# esquematico_ED3.net
KiCad netlist of a schematic drawn in Altium Designer
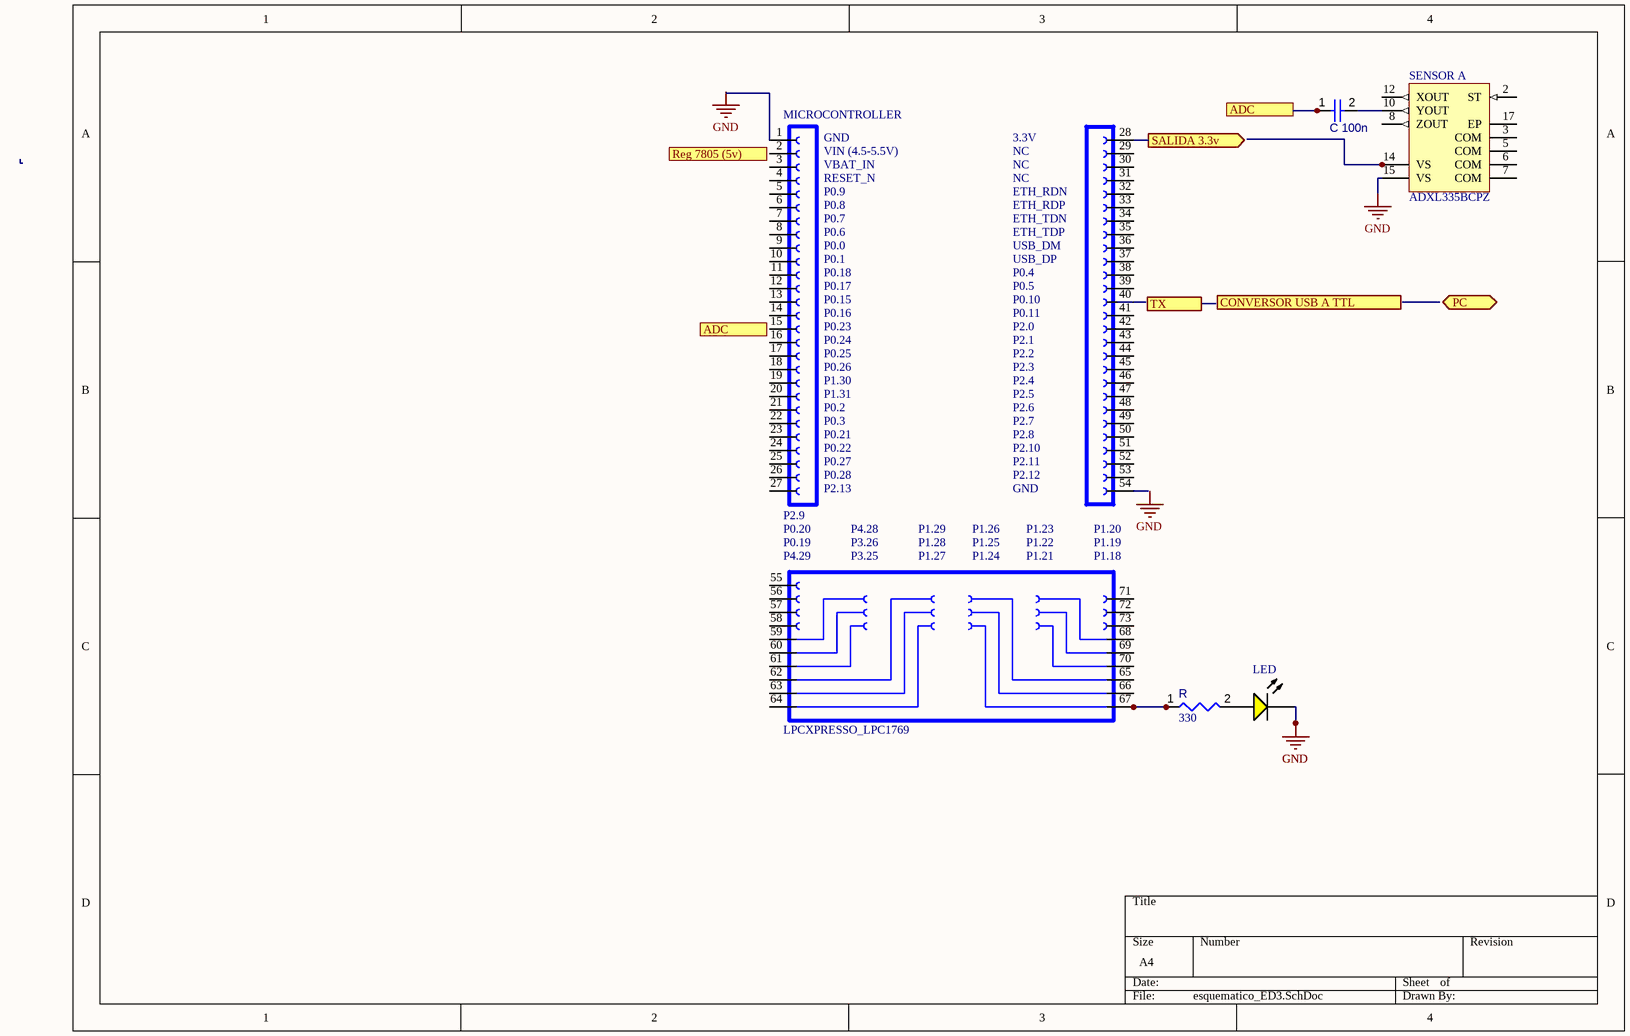
[diagram p0: esquematico_ED3.SchDoc]

(export (version "E")
  (design (tool "Eeschema 10.0.6"))
  (components
    (comp (ref "C 100n")
      (value "Capacitors")
      (description "Capacitor")
      (libsource (lib "Juana Pucheta Noguera") (part "CAP-NP-2"))
    )
    (comp (ref "LED")
      (value "~")
      (footprint "VISH-TLMX1100-2_V")
      (description "Yellow LED, 20 mA, 2.1 V, -40 to 100 degC, 2-Pin SMD (0603), RoHS, Tape and Reel")
      (fields (field (name "MANUFACTURER") "Vishay Semiconductor") (field (name "POWER") "90mW"))
      (libsource (lib "Juana Pucheta Noguera") (part "LED-YELLOW-AK-2"))
    )
    (comp (ref "MICROCONTROLLER")
      (value "LPCXPRESSO_LPC1769")
      (footprint "LPCXPRESSO_LPC1769")
      (fields (field (name "MF") "Embedded Artists") (field (name "MP") "LPCXPRESSO LPC1769"))
      (libsource (lib "LPCXPRESSO_LPC1769 (1)") (part "LPCXPRESSO_LPC1769"))
    )
    (comp (ref "R")
      (value "330")
      (footprint "RESC0402(1005)_L")
      (description "330R 0.063W 5% 0402 (1005 Metric)  SMD")
      (fields (field (name "TOLERANCE") "5%") (field (name "POWER") "63mW"))
      (libsource (lib "Juana Pucheta Noguera") (part "330R2J"))
    )
    (comp (ref "SENSOR")
      (value "ADXL335BCPZ")
      (footprint "ADI-CP-16-14_M")
      (fields (field (name "MANUFACTURER") "Analog Devices"))
      (libsource (lib "Juana Pucheta Noguera") (part "ADI-ADXL3XX-CP-16-XX"))
    )
  )
  (nets
    (net (code "5") (name "/SALIDA 3.3v") (class "Default")
      (node (ref "MICROCONTROLLER") (pin "28") (pinfunction "28_28") (pintype "passive"))
    )
    (net (code "7") (name "GND") (class "Default")
      (node (ref "LED") (pin "2") (pinfunction "K_2") (pintype "passive"))
      (node (ref "SENSOR") (pin "15") (pinfunction "VS_15") (pintype "power_in"))
    )
    (net (code "8") (name "Net-(MICROCONTROLLER-Pad67)") (class "Default")
      (node (ref "MICROCONTROLLER") (pin "67") (pinfunction "67_67") (pintype "passive"))
      (node (ref "R") (pin "1") (pinfunction "1_1") (pintype "passive"))
    )
    (net (code "9") (name "Net-(SENSORA-YOUT)") (class "Default")
      (node (ref "C 100n") (pin "2") (pinfunction "2_2") (pintype "passive"))
      (node (ref "SENSOR") (pin "10") (pinfunction "YOUT_10") (pintype "output"))
    )
    (net (code "10") (name "unconnected-(C 100n-Pad1)") (class "Default")
      (node (ref "C 100n") (pin "1") (pinfunction "1_1") (pintype "passive"))
    )
    (net (code "11") (name "unconnected-(LED-A-Pad1)") (class "Default")
      (node (ref "LED") (pin "1") (pinfunction "A_1") (pintype "passive"))
    )
    (net (code "12") (name "unconnected-(MICROCONTROLLER-Pad1)") (class "Default")
      (node (ref "MICROCONTROLLER") (pin "1") (pinfunction "1_1") (pintype "passive"))
    )
    (net (code "13") (name "unconnected-(MICROCONTROLLER-Pad2)") (class "Default")
      (node (ref "MICROCONTROLLER") (pin "2") (pinfunction "2_2") (pintype "passive"))
    )
    (net (code "14") (name "unconnected-(MICROCONTROLLER-Pad3)") (class "Default")
      (node (ref "MICROCONTROLLER") (pin "3") (pinfunction "3_3") (pintype "passive"))
    )
    (net (code "15") (name "unconnected-(MICROCONTROLLER-Pad4)") (class "Default")
      (node (ref "MICROCONTROLLER") (pin "4") (pinfunction "4_4") (pintype "passive"))
    )
    (net (code "16") (name "unconnected-(MICROCONTROLLER-Pad5)") (class "Default")
      (node (ref "MICROCONTROLLER") (pin "5") (pinfunction "5_5") (pintype "passive"))
    )
    (net (code "17") (name "unconnected-(MICROCONTROLLER-Pad6)") (class "Default")
      (node (ref "MICROCONTROLLER") (pin "6") (pinfunction "6_6") (pintype "passive"))
    )
    (net (code "18") (name "unconnected-(MICROCONTROLLER-Pad7)") (class "Default")
      (node (ref "MICROCONTROLLER") (pin "7") (pinfunction "7_7") (pintype "passive"))
    )
    (net (code "19") (name "unconnected-(MICROCONTROLLER-Pad8)") (class "Default")
      (node (ref "MICROCONTROLLER") (pin "8") (pinfunction "8_8") (pintype "passive"))
    )
    (net (code "20") (name "unconnected-(MICROCONTROLLER-Pad9)") (class "Default")
      (node (ref "MICROCONTROLLER") (pin "9") (pinfunction "9_9") (pintype "passive"))
    )
    (net (code "21") (name "unconnected-(MICROCONTROLLER-Pad10)") (class "Default")
      (node (ref "MICROCONTROLLER") (pin "10") (pinfunction "10_10") (pintype "passive"))
    )
    (net (code "22") (name "unconnected-(MICROCONTROLLER-Pad11)") (class "Default")
      (node (ref "MICROCONTROLLER") (pin "11") (pinfunction "11_11") (pintype "passive"))
    )
    (net (code "23") (name "unconnected-(MICROCONTROLLER-Pad12)") (class "Default")
      (node (ref "MICROCONTROLLER") (pin "12") (pinfunction "12_12") (pintype "passive"))
    )
    (net (code "24") (name "unconnected-(MICROCONTROLLER-Pad13)") (class "Default")
      (node (ref "MICROCONTROLLER") (pin "13") (pinfunction "13_13") (pintype "passive"))
    )
    (net (code "25") (name "unconnected-(MICROCONTROLLER-Pad14)") (class "Default")
      (node (ref "MICROCONTROLLER") (pin "14") (pinfunction "14_14") (pintype "passive"))
    )
    (net (code "26") (name "unconnected-(MICROCONTROLLER-Pad15)") (class "Default")
      (node (ref "MICROCONTROLLER") (pin "15") (pinfunction "15_15") (pintype "passive"))
    )
    (net (code "27") (name "unconnected-(MICROCONTROLLER-Pad16)") (class "Default")
      (node (ref "MICROCONTROLLER") (pin "16") (pinfunction "16_16") (pintype "passive"))
    )
    (net (code "28") (name "unconnected-(MICROCONTROLLER-Pad17)") (class "Default")
      (node (ref "MICROCONTROLLER") (pin "17") (pinfunction "17_17") (pintype "passive"))
    )
    (net (code "29") (name "unconnected-(MICROCONTROLLER-Pad18)") (class "Default")
      (node (ref "MICROCONTROLLER") (pin "18") (pinfunction "18_18") (pintype "passive"))
    )
    (net (code "30") (name "unconnected-(MICROCONTROLLER-Pad19)") (class "Default")
      (node (ref "MICROCONTROLLER") (pin "19") (pinfunction "19_19") (pintype "passive"))
    )
    (net (code "31") (name "unconnected-(MICROCONTROLLER-Pad20)") (class "Default")
      (node (ref "MICROCONTROLLER") (pin "20") (pinfunction "20_20") (pintype "passive"))
    )
    (net (code "32") (name "unconnected-(MICROCONTROLLER-Pad21)") (class "Default")
      (node (ref "MICROCONTROLLER") (pin "21") (pinfunction "21_21") (pintype "passive"))
    )
    (net (code "33") (name "unconnected-(MICROCONTROLLER-Pad22)") (class "Default")
      (node (ref "MICROCONTROLLER") (pin "22") (pinfunction "22_22") (pintype "passive"))
    )
    (net (code "34") (name "unconnected-(MICROCONTROLLER-Pad23)") (class "Default")
      (node (ref "MICROCONTROLLER") (pin "23") (pinfunction "23_23") (pintype "passive"))
    )
    (net (code "35") (name "unconnected-(MICROCONTROLLER-Pad24)") (class "Default")
      (node (ref "MICROCONTROLLER") (pin "24") (pinfunction "24_24") (pintype "passive"))
    )
    (net (code "36") (name "unconnected-(MICROCONTROLLER-Pad25)") (class "Default")
      (node (ref "MICROCONTROLLER") (pin "25") (pinfunction "25_25") (pintype "passive"))
    )
    (net (code "37") (name "unconnected-(MICROCONTROLLER-Pad26)") (class "Default")
      (node (ref "MICROCONTROLLER") (pin "26") (pinfunction "26_26") (pintype "passive"))
    )
    (net (code "38") (name "unconnected-(MICROCONTROLLER-Pad27)") (class "Default")
      (node (ref "MICROCONTROLLER") (pin "27") (pinfunction "27_27") (pintype "passive"))
    )
    (net (code "39") (name "unconnected-(MICROCONTROLLER-Pad29)") (class "Default")
      (node (ref "MICROCONTROLLER") (pin "29") (pinfunction "29_29") (pintype "passive"))
    )
    (net (code "40") (name "unconnected-(MICROCONTROLLER-Pad30)") (class "Default")
      (node (ref "MICROCONTROLLER") (pin "30") (pinfunction "30_30") (pintype "passive"))
    )
    (net (code "41") (name "unconnected-(MICROCONTROLLER-Pad31)") (class "Default")
      (node (ref "MICROCONTROLLER") (pin "31") (pinfunction "31_31") (pintype "passive"))
    )
    (net (code "42") (name "unconnected-(MICROCONTROLLER-Pad32)") (class "Default")
      (node (ref "MICROCONTROLLER") (pin "32") (pinfunction "32_32") (pintype "passive"))
    )
    (net (code "43") (name "unconnected-(MICROCONTROLLER-Pad33)") (class "Default")
      (node (ref "MICROCONTROLLER") (pin "33") (pinfunction "33_33") (pintype "passive"))
    )
    (net (code "44") (name "unconnected-(MICROCONTROLLER-Pad34)") (class "Default")
      (node (ref "MICROCONTROLLER") (pin "34") (pinfunction "34_34") (pintype "passive"))
    )
    (net (code "45") (name "unconnected-(MICROCONTROLLER-Pad35)") (class "Default")
      (node (ref "MICROCONTROLLER") (pin "35") (pinfunction "35_35") (pintype "passive"))
    )
    (net (code "46") (name "unconnected-(MICROCONTROLLER-Pad36)") (class "Default")
      (node (ref "MICROCONTROLLER") (pin "36") (pinfunction "36_36") (pintype "passive"))
    )
    (net (code "47") (name "unconnected-(MICROCONTROLLER-Pad37)") (class "Default")
      (node (ref "MICROCONTROLLER") (pin "37") (pinfunction "37_37") (pintype "passive"))
    )
    (net (code "48") (name "unconnected-(MICROCONTROLLER-Pad38)") (class "Default")
      (node (ref "MICROCONTROLLER") (pin "38") (pinfunction "38_38") (pintype "passive"))
    )
    (net (code "49") (name "unconnected-(MICROCONTROLLER-Pad39)") (class "Default")
      (node (ref "MICROCONTROLLER") (pin "39") (pinfunction "39_39") (pintype "passive"))
    )
    (net (code "50") (name "unconnected-(MICROCONTROLLER-Pad40)") (class "Default")
      (node (ref "MICROCONTROLLER") (pin "40") (pinfunction "40_40") (pintype "passive"))
    )
    (net (code "51") (name "unconnected-(MICROCONTROLLER-Pad41)") (class "Default")
      (node (ref "MICROCONTROLLER") (pin "41") (pinfunction "41_41") (pintype "passive"))
    )
    (net (code "52") (name "unconnected-(MICROCONTROLLER-Pad42)") (class "Default")
      (node (ref "MICROCONTROLLER") (pin "42") (pinfunction "42_42") (pintype "passive"))
    )
    (net (code "53") (name "unconnected-(MICROCONTROLLER-Pad43)") (class "Default")
      (node (ref "MICROCONTROLLER") (pin "43") (pinfunction "43_43") (pintype "passive"))
    )
    (net (code "54") (name "unconnected-(MICROCONTROLLER-Pad44)") (class "Default")
      (node (ref "MICROCONTROLLER") (pin "44") (pinfunction "44_44") (pintype "passive"))
    )
    (net (code "55") (name "unconnected-(MICROCONTROLLER-Pad45)") (class "Default")
      (node (ref "MICROCONTROLLER") (pin "45") (pinfunction "45_45") (pintype "passive"))
    )
    (net (code "56") (name "unconnected-(MICROCONTROLLER-Pad46)") (class "Default")
      (node (ref "MICROCONTROLLER") (pin "46") (pinfunction "46_46") (pintype "passive"))
    )
    (net (code "57") (name "unconnected-(MICROCONTROLLER-Pad47)") (class "Default")
      (node (ref "MICROCONTROLLER") (pin "47") (pinfunction "47_47") (pintype "passive"))
    )
    (net (code "58") (name "unconnected-(MICROCONTROLLER-Pad48)") (class "Default")
      (node (ref "MICROCONTROLLER") (pin "48") (pinfunction "48_48") (pintype "passive"))
    )
    (net (code "59") (name "unconnected-(MICROCONTROLLER-Pad49)") (class "Default")
      (node (ref "MICROCONTROLLER") (pin "49") (pinfunction "49_49") (pintype "passive"))
    )
    (net (code "60") (name "unconnected-(MICROCONTROLLER-Pad50)") (class "Default")
      (node (ref "MICROCONTROLLER") (pin "50") (pinfunction "50_50") (pintype "passive"))
    )
    (net (code "61") (name "unconnected-(MICROCONTROLLER-Pad51)") (class "Default")
      (node (ref "MICROCONTROLLER") (pin "51") (pinfunction "51_51") (pintype "passive"))
    )
    (net (code "62") (name "unconnected-(MICROCONTROLLER-Pad52)") (class "Default")
      (node (ref "MICROCONTROLLER") (pin "52") (pinfunction "52_52") (pintype "passive"))
    )
    (net (code "63") (name "unconnected-(MICROCONTROLLER-Pad53)") (class "Default")
      (node (ref "MICROCONTROLLER") (pin "53") (pinfunction "53_53") (pintype "passive"))
    )
    (net (code "64") (name "unconnected-(MICROCONTROLLER-Pad54)") (class "Default")
      (node (ref "MICROCONTROLLER") (pin "54") (pinfunction "54_54") (pintype "passive"))
    )
    (net (code "65") (name "unconnected-(MICROCONTROLLER-Pad55)") (class "Default")
      (node (ref "MICROCONTROLLER") (pin "55") (pinfunction "55_55") (pintype "passive"))
    )
    (net (code "66") (name "unconnected-(MICROCONTROLLER-Pad56)") (class "Default")
      (node (ref "MICROCONTROLLER") (pin "56") (pinfunction "56_56") (pintype "passive"))
    )
    (net (code "67") (name "unconnected-(MICROCONTROLLER-Pad57)") (class "Default")
      (node (ref "MICROCONTROLLER") (pin "57") (pinfunction "57_57") (pintype "passive"))
    )
    (net (code "68") (name "unconnected-(MICROCONTROLLER-Pad58)") (class "Default")
      (node (ref "MICROCONTROLLER") (pin "58") (pinfunction "58_58") (pintype "passive"))
    )
    (net (code "69") (name "unconnected-(MICROCONTROLLER-Pad59)") (class "Default")
      (node (ref "MICROCONTROLLER") (pin "59") (pinfunction "59_59") (pintype "passive"))
    )
    (net (code "70") (name "unconnected-(MICROCONTROLLER-Pad60)") (class "Default")
      (node (ref "MICROCONTROLLER") (pin "60") (pinfunction "60_60") (pintype "passive"))
    )
    (net (code "71") (name "unconnected-(MICROCONTROLLER-Pad61)") (class "Default")
      (node (ref "MICROCONTROLLER") (pin "61") (pinfunction "61_61") (pintype "passive"))
    )
    (net (code "72") (name "unconnected-(MICROCONTROLLER-Pad62)") (class "Default")
      (node (ref "MICROCONTROLLER") (pin "62") (pinfunction "62_62") (pintype "passive"))
    )
    (net (code "73") (name "unconnected-(MICROCONTROLLER-Pad63)") (class "Default")
      (node (ref "MICROCONTROLLER") (pin "63") (pinfunction "63_63") (pintype "passive"))
    )
    (net (code "74") (name "unconnected-(MICROCONTROLLER-Pad64)") (class "Default")
      (node (ref "MICROCONTROLLER") (pin "64") (pinfunction "64_64") (pintype "passive"))
    )
    (net (code "75") (name "unconnected-(MICROCONTROLLER-Pad65)") (class "Default")
      (node (ref "MICROCONTROLLER") (pin "65") (pinfunction "65_65") (pintype "passive"))
    )
    (net (code "76") (name "unconnected-(MICROCONTROLLER-Pad66)") (class "Default")
      (node (ref "MICROCONTROLLER") (pin "66") (pinfunction "66_66") (pintype "passive"))
    )
    (net (code "77") (name "unconnected-(MICROCONTROLLER-Pad68)") (class "Default")
      (node (ref "MICROCONTROLLER") (pin "68") (pinfunction "68_68") (pintype "passive"))
    )
    (net (code "78") (name "unconnected-(MICROCONTROLLER-Pad69)") (class "Default")
      (node (ref "MICROCONTROLLER") (pin "69") (pinfunction "69_69") (pintype "passive"))
    )
    (net (code "79") (name "unconnected-(MICROCONTROLLER-Pad70)") (class "Default")
      (node (ref "MICROCONTROLLER") (pin "70") (pinfunction "70_70") (pintype "passive"))
    )
    (net (code "80") (name "unconnected-(MICROCONTROLLER-Pad71)") (class "Default")
      (node (ref "MICROCONTROLLER") (pin "71") (pinfunction "71_71") (pintype "passive"))
    )
    (net (code "81") (name "unconnected-(MICROCONTROLLER-Pad72)") (class "Default")
      (node (ref "MICROCONTROLLER") (pin "72") (pinfunction "72_72") (pintype "passive"))
    )
    (net (code "82") (name "unconnected-(MICROCONTROLLER-Pad73)") (class "Default")
      (node (ref "MICROCONTROLLER") (pin "73") (pinfunction "73_73") (pintype "passive"))
    )
    (net (code "83") (name "unconnected-(R-Pad2)") (class "Default")
      (node (ref "R") (pin "2") (pinfunction "2_2") (pintype "passive"))
    )
    (net (code "84") (name "unconnected-(SENSORA-COM-Pad3)") (class "Default")
      (node (ref "SENSOR") (pin "3") (pinfunction "COM_3") (pintype "power_in"))
    )
    (net (code "85") (name "unconnected-(SENSORA-COM-Pad5)") (class "Default")
      (node (ref "SENSOR") (pin "5") (pinfunction "COM_5") (pintype "power_in"))
    )
    (net (code "86") (name "unconnected-(SENSORA-COM-Pad6)") (class "Default")
      (node (ref "SENSOR") (pin "6") (pinfunction "COM_6") (pintype "power_in"))
    )
    (net (code "87") (name "unconnected-(SENSORA-COM-Pad7)") (class "Default")
      (node (ref "SENSOR") (pin "7") (pinfunction "COM_7") (pintype "power_in"))
    )
    (net (code "88") (name "unconnected-(SENSORA-EP-Pad17)") (class "Default")
      (node (ref "SENSOR") (pin "17") (pinfunction "EP_17") (pintype "passive"))
    )
    (net (code "89") (name "unconnected-(SENSORA-ST-Pad2)") (class "Default")
      (node (ref "SENSOR") (pin "2") (pinfunction "ST_2") (pintype "input"))
    )
    (net (code "90") (name "unconnected-(SENSORA-VS-Pad14)") (class "Default")
      (node (ref "SENSOR") (pin "14") (pinfunction "VS_14") (pintype "power_in"))
    )
    (net (code "91") (name "unconnected-(SENSORA-XOUT-Pad12)") (class "Default")
      (node (ref "SENSOR") (pin "12") (pinfunction "XOUT_12") (pintype "output"))
    )
    (net (code "92") (name "unconnected-(SENSORA-ZOUT-Pad8)") (class "Default")
      (node (ref "SENSOR") (pin "8") (pinfunction "ZOUT_8") (pintype "output"))
    )
  )
)
